# SR1PCB_2025-01-31.net
KiCad netlist of a schematic drawn in Altium Designer
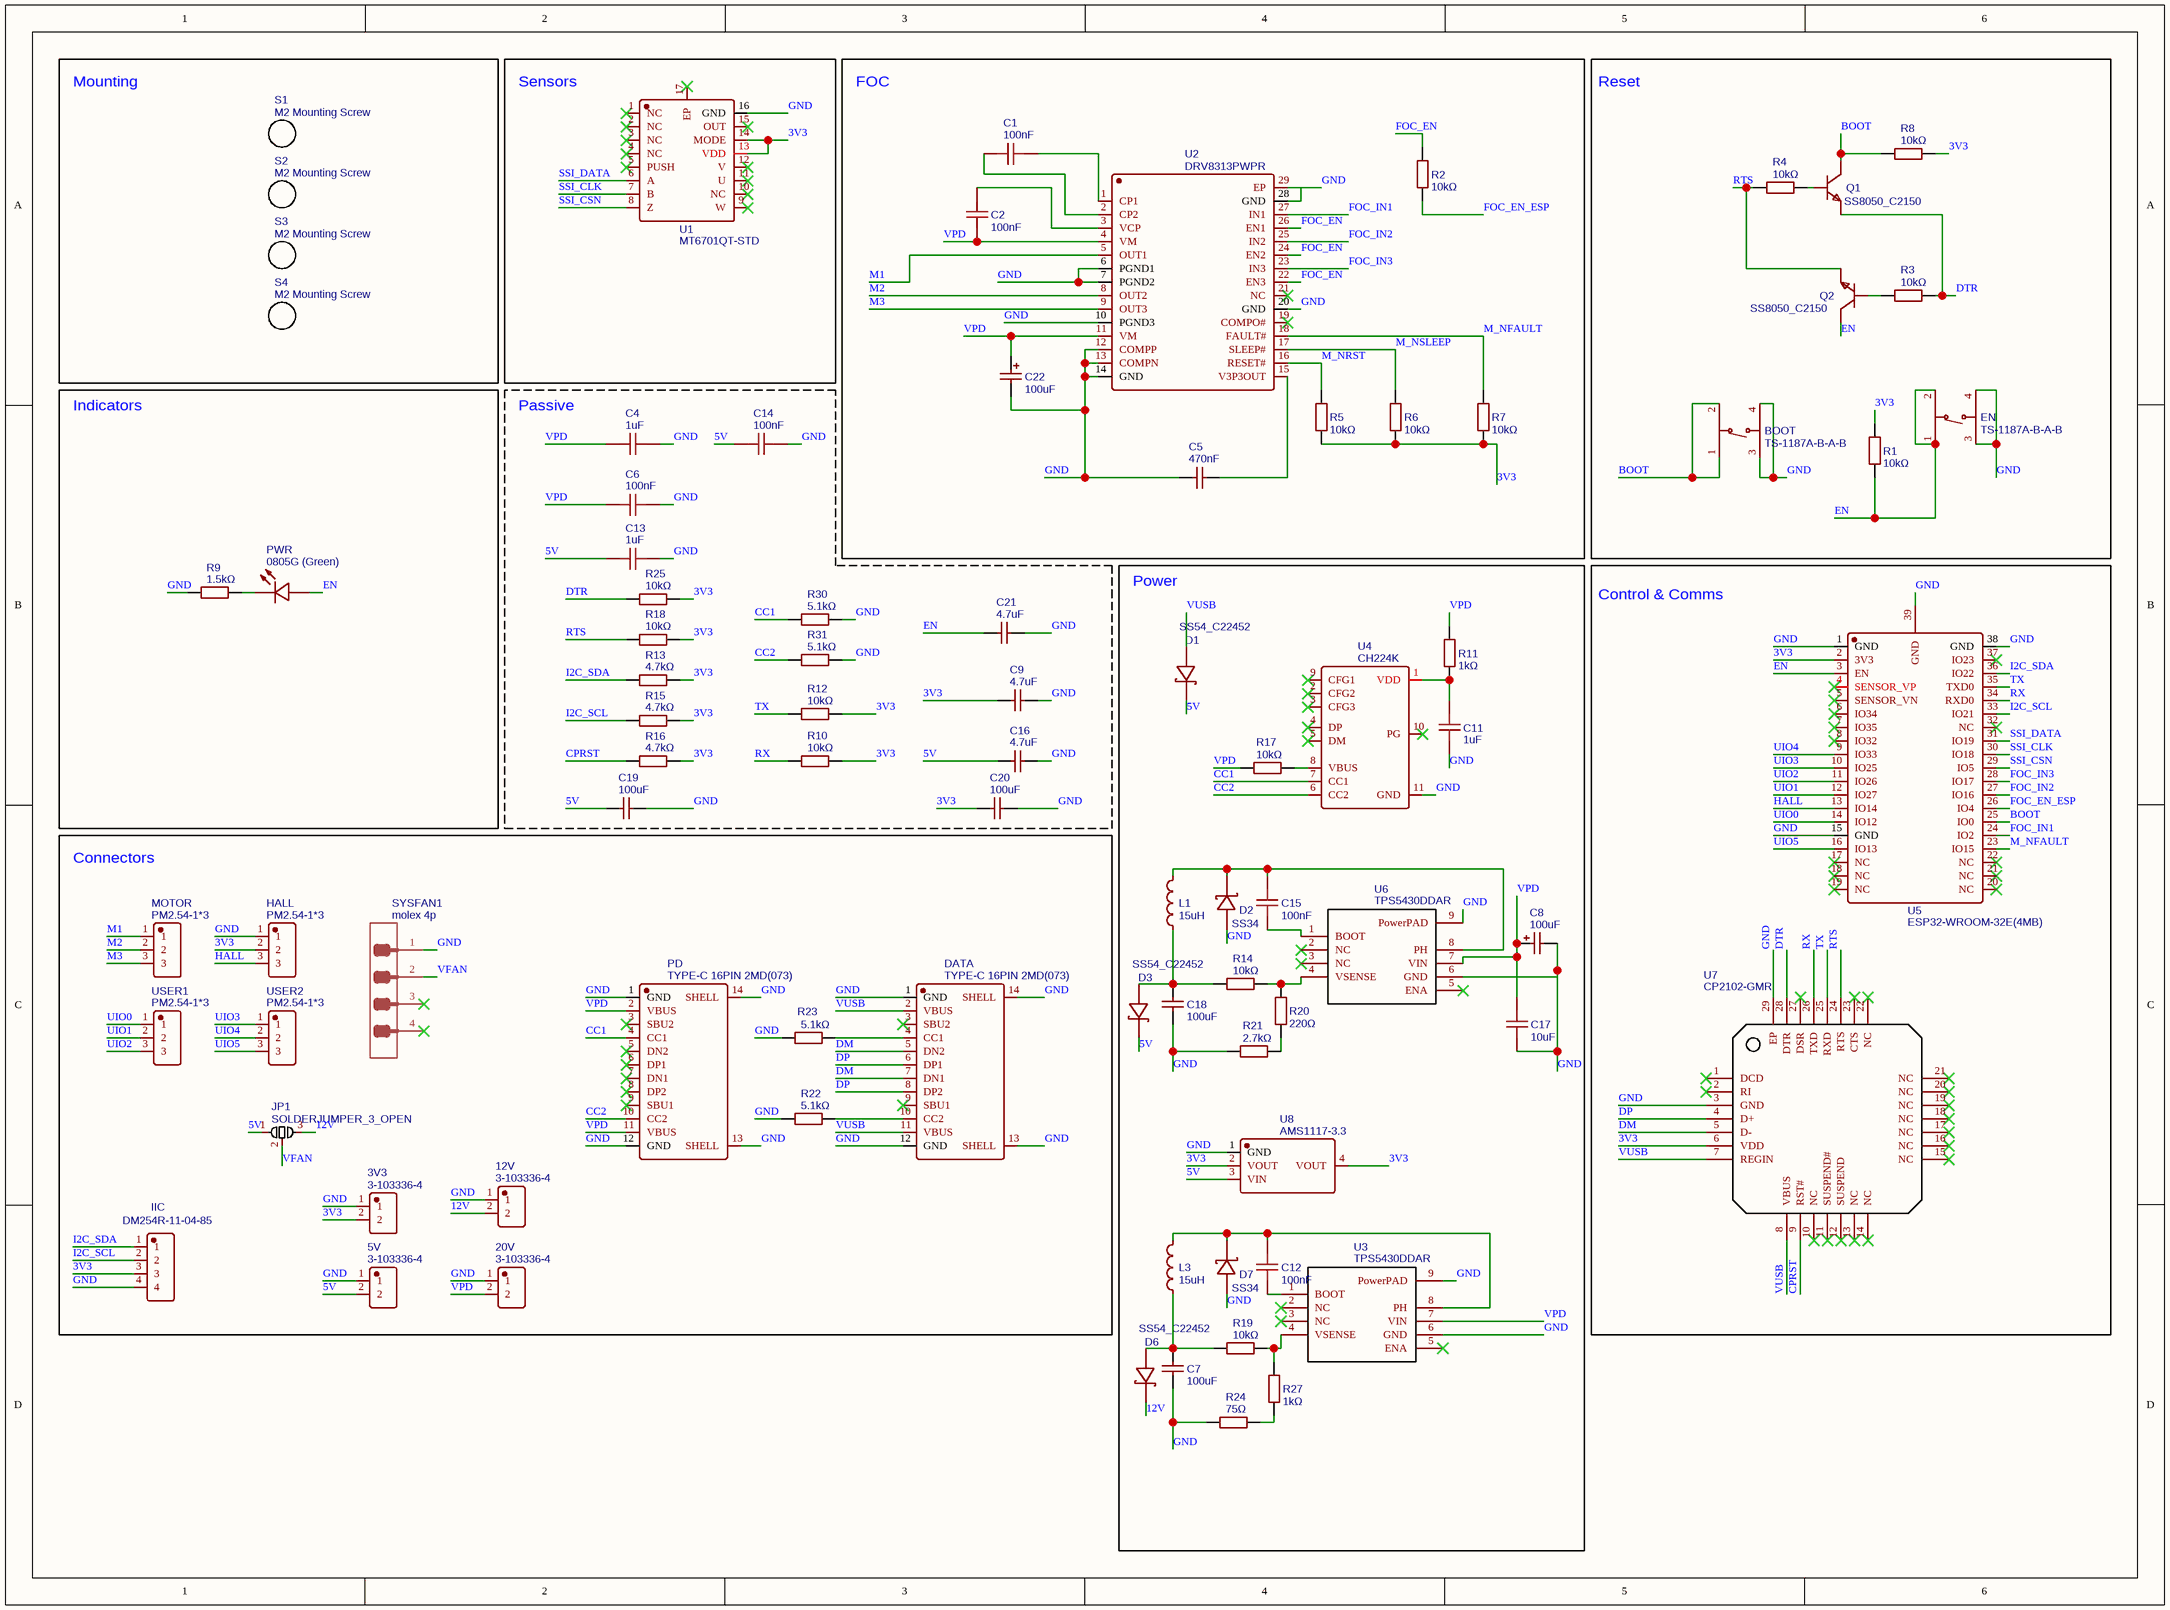
[diagram p0: SR1PCB_2025-01-31.schdoc]

(export (version "E")
  (design (tool "Eeschema 10.0.6"))
  (components
    (comp (ref "3V3")
      (value "3-103336-4")
      (fields (field (name "MANUFACTURER") "TE Connectivity(泰科电子)") (field (name "CONTRIBUTOR") "lcsc"))
      (libsource (lib "altium-import") (part "root_0_3-103336-4_"))
    )
    (comp (ref "5V")
      (value "3-103336-4")
      (fields (field (name "MANUFACTURER") "TE Connectivity(泰科电子)") (field (name "CONTRIBUTOR") "lcsc"))
      (libsource (lib "altium-import") (part "root_0_3-103336-4_"))
    )
    (comp (ref "12V")
      (value "3-103336-4")
      (fields (field (name "MANUFACTURER") "TE Connectivity(泰科电子)") (field (name "CONTRIBUTOR") "lcsc"))
      (libsource (lib "altium-import") (part "root_0_3-103336-4_"))
    )
    (comp (ref "20V")
      (value "3-103336-4")
      (fields (field (name "MANUFACTURER") "TE Connectivity(泰科电子)") (field (name "CONTRIBUTOR") "lcsc"))
      (libsource (lib "altium-import") (part "root_0_3-103336-4_"))
    )
    (comp (ref "BOOT")
      (value "TS-1187A-B-A-B")
      (fields (field (name "MANUFACTURER") "XKB Connectivity(中国星坤)") (field (name "CONTRIBUTOR") "LCSC"))
      (libsource (lib "altium-import") (part "root_1_TS-1187A-B-A-B_"))
    )
    (comp (ref "C1")
      (value "100nF")
      (fields
        (field (name "MANUFACTURER") "YAGEO(国巨)")
        (field (name "MANUFACTURER PART") "CC0603KRX7R9BB104")
      )
      (libsource (lib "altium-import") (part "root_0_100nF_"))
    )
    (comp (ref "C2")
      (value "100nF")
      (fields
        (field (name "MANUFACTURER") "YAGEO(国巨)")
        (field (name "MANUFACTURER PART") "CC0603KRX7R9BB104")
      )
      (libsource (lib "altium-import") (part "root_1_100nF_"))
    )
    (comp (ref "C4")
      (value "1uF")
      (fields
        (field (name "MANUFACTURER PART") "CL10A105KB8NNNC")
        (field (name "MANUFACTURER") "SAMSUNG(三星)")
      )
      (libsource (lib "altium-import") (part "root_0_1uF_"))
    )
    (comp (ref "C5")
      (value "470nF")
      (fields
        (field (name "MANUFACTURER PART") "CL21B474KBFNNNE")
        (field (name "MANUFACTURER") "SAMSUNG(三星)")
        (field (name "CONTRIBUTOR") "eisendev")
      )
      (libsource (lib "altium-import") (part "root_3_470nF_"))
    )
    (comp (ref "C6")
      (value "100nF")
      (fields
        (field (name "MANUFACTURER") "YAGEO(国巨)")
        (field (name "MANUFACTURER PART") "CC0603KRX7R9BB104")
      )
      (libsource (lib "altium-import") (part "root_0_100nF_"))
    )
    (comp (ref "C7")
      (value "100uF")
      (fields
        (field (name "MANUFACTURER PART") "CL31A107MQHNNNE")
        (field (name "MANUFACTURER") "SAMSUNG(三星)")
      )
      (libsource (lib "altium-import") (part "root_1_100uF_"))
    )
    (comp (ref "C8")
      (value "100uF")
      (fields (field (name "MANUFACTURER") "PANASONIC(松下)") (field (name "MANUFACTURER PART") "20TQC100MYF"))
      (libsource (lib "altium-import") (part "root_2_100uF_"))
    )
    (comp (ref "C9")
      (value "4.7uF")
      (fields
        (field (name "MANUFACTURER PART") "CL05A475MP5NRNC")
        (field (name "MANUFACTURER") "SAMSUNG(三星)")
      )
      (libsource (lib "altium-import") (part "root_0_4.7uF_"))
    )
    (comp (ref "C11")
      (value "1uF")
      (fields
        (field (name "MANUFACTURER PART") "CL10A105KB8NNNC")
        (field (name "MANUFACTURER") "SAMSUNG(三星)")
      )
      (libsource (lib "altium-import") (part "root_1_1uF_"))
    )
    (comp (ref "C12")
      (value "100nF")
      (fields
        (field (name "MANUFACTURER") "YAGEO(国巨)")
        (field (name "MANUFACTURER PART") "CC0603KRX7R9BB104")
      )
      (libsource (lib "altium-import") (part "root_3_100nF_"))
    )
    (comp (ref "C13")
      (value "1uF")
      (fields
        (field (name "MANUFACTURER PART") "CL10A105KB8NNNC")
        (field (name "MANUFACTURER") "SAMSUNG(三星)")
      )
      (libsource (lib "altium-import") (part "root_0_1uF_"))
    )
    (comp (ref "C14")
      (value "100nF")
      (fields
        (field (name "MANUFACTURER") "YAGEO(国巨)")
        (field (name "MANUFACTURER PART") "CC0603KRX7R9BB104")
      )
      (libsource (lib "altium-import") (part "root_0_100nF_"))
    )
    (comp (ref "C15")
      (value "100nF")
      (fields
        (field (name "MANUFACTURER") "YAGEO(国巨)")
        (field (name "MANUFACTURER PART") "CC0603KRX7R9BB104")
      )
      (libsource (lib "altium-import") (part "root_3_100nF_"))
    )
    (comp (ref "C16")
      (value "4.7uF")
      (fields
        (field (name "MANUFACTURER PART") "CL05A475MP5NRNC")
        (field (name "MANUFACTURER") "SAMSUNG(三星)")
      )
      (libsource (lib "altium-import") (part "root_0_4.7uF_"))
    )
    (comp (ref "C17")
      (value "10uF")
      (fields
        (field (name "MANUFACTURER PART") "CL21A106KAYNNNE")
        (field (name "MANUFACTURER") "SAMSUNG(三星)")
      )
      (libsource (lib "altium-import") (part "root_1_10uF_"))
    )
    (comp (ref "C18")
      (value "100uF")
      (fields
        (field (name "MANUFACTURER PART") "CL31A107MQHNNNE")
        (field (name "MANUFACTURER") "SAMSUNG(三星)")
      )
      (libsource (lib "altium-import") (part "root_1_100uF_"))
    )
    (comp (ref "C19")
      (value "100uF")
      (fields
        (field (name "MANUFACTURER PART") "CL31A107MQHNNNE")
        (field (name "MANUFACTURER") "SAMSUNG(三星)")
      )
      (libsource (lib "altium-import") (part "root_0_100uF_"))
    )
    (comp (ref "C20")
      (value "100uF")
      (fields
        (field (name "MANUFACTURER PART") "CL31A107MQHNNNE")
        (field (name "MANUFACTURER") "SAMSUNG(三星)")
      )
      (libsource (lib "altium-import") (part "root_0_100uF_"))
    )
    (comp (ref "C21")
      (value "4.7uF")
      (fields
        (field (name "MANUFACTURER PART") "CL05A475MP5NRNC")
        (field (name "MANUFACTURER") "SAMSUNG(三星)")
      )
      (libsource (lib "altium-import") (part "root_0_4.7uF_"))
    )
    (comp (ref "C22")
      (value "100uF")
      (fields (field (name "MANUFACTURER") "PANASONIC(松下)") (field (name "MANUFACTURER PART") "20TQC100MYF"))
      (libsource (lib "") (part "root_1_100uF__1"))
    )
    (comp (ref "D1")
      (value "SS54_C22452")
      (fields
        (field (name "MANUFACTURER PART") "SS54")
        (field (name "MANUFACTURER") "MDD")
        (field (name "CONTRIBUTOR") "mtz8302")
      )
      (libsource (lib "altium-import") (part "root_3_SS54_C22452_"))
    )
    (comp (ref "D2")
      (value "SS34")
      (fields (field (name "MANUFACTURER") "MDD(辰达半导体)"))
      (libsource (lib "altium-import") (part "root_3_SS34_"))
    )
    (comp (ref "D3")
      (value "SS54_C22452")
      (fields
        (field (name "MANUFACTURER PART") "SS54")
        (field (name "MANUFACTURER") "MDD")
        (field (name "CONTRIBUTOR") "mtz8302")
      )
      (libsource (lib "altium-import") (part "root_3_SS54_C22452_"))
    )
    (comp (ref "D6")
      (value "SS54_C22452")
      (fields
        (field (name "MANUFACTURER PART") "SS54")
        (field (name "MANUFACTURER") "MDD")
        (field (name "CONTRIBUTOR") "mtz8302")
      )
      (libsource (lib "altium-import") (part "root_3_SS54_C22452_"))
    )
    (comp (ref "D7")
      (value "SS34")
      (fields (field (name "MANUFACTURER") "MDD(辰达半导体)"))
      (libsource (lib "altium-import") (part "root_3_SS34_"))
    )
    (comp (ref "DATA")
      (value "TYPE-C 16PIN 2MD(073)")
      (fields (field (name "MANUFACTURER") "SHOU HAN(首韩)") (field (name "CONTRIBUTOR") "LCSC"))
      (libsource (lib "altium-import") (part "root_0_TYPE-C 16PIN 2MD(073)_"))
    )
    (comp (ref "EN")
      (value "TS-1187A-B-A-B")
      (fields (field (name "MANUFACTURER") "XKB Connectivity(中国星坤)") (field (name "CONTRIBUTOR") "LCSC"))
      (libsource (lib "altium-import") (part "root_1_TS-1187A-B-A-B_"))
    )
    (comp (ref "HALL")
      (value "PM2.54-1*3")
      (fields (field (name "MANUFACTURER") "ZHOURI(洲日)") (field (name "CONTRIBUTOR") "lcsc"))
      (libsource (lib "altium-import") (part "root_0_PM2.54-1*3_"))
    )
    (comp (ref "IIC")
      (value "DM254R-11-04-85")
      (fields (field (name "MANUFACTURER") "DEALON(德艺隆)") (field (name "CONTRIBUTOR") "LCSC"))
      (libsource (lib "altium-import") (part "root_0_DM254R-11-04-85_"))
    )
    (comp (ref "JP1")
      (value "SOLDERJUMPER_3_OPEN")
      (fields (field (name "CONTRIBUTOR") "mtz8302"))
      (libsource (lib "altium-import") (part "root_0_SOLDERJUMPER_3_OPEN_"))
    )
    (comp (ref "L1")
      (value "15uH")
      (fields
        (field (name "MANUFACTURER") "Sunlord(顺络)")
        (field (name "MANUFACTURER PART") "MWSA0603S-150MT")
        (field (name "CONTRIBUTOR") "LCSC")
      )
      (libsource (lib "altium-import") (part "root_1_15uH_"))
    )
    (comp (ref "L3")
      (value "15uH")
      (fields
        (field (name "MANUFACTURER") "Sunlord(顺络)")
        (field (name "MANUFACTURER PART") "MWSA0603S-150MT")
        (field (name "CONTRIBUTOR") "LCSC")
      )
      (libsource (lib "altium-import") (part "root_1_15uH_"))
    )
    (comp (ref "MOTOR")
      (value "PM2.54-1*3")
      (fields (field (name "MANUFACTURER") "ZHOURI(洲日)") (field (name "CONTRIBUTOR") "lcsc"))
      (libsource (lib "altium-import") (part "root_0_PM2.54-1*3_"))
    )
    (comp (ref "PD")
      (value "TYPE-C 16PIN 2MD(073)")
      (fields (field (name "MANUFACTURER") "SHOU HAN(首韩)") (field (name "CONTRIBUTOR") "LCSC"))
      (libsource (lib "altium-import") (part "root_0_TYPE-C 16PIN 2MD(073)_"))
    )
    (comp (ref "PWR")
      (value "0805G (Green)")
      (fields (field (name "MANUFACTURER") "KENTO") (field (name "MANUFACTURER PART") "KT-0805G"))
      (libsource (lib "altium-import") (part "root_0_0805G (Green)_"))
    )
    (comp (ref "Q1")
      (value "SS8050_C2150")
      (fields (field (name "MANUFACTURER") "CJ(江苏长电/长晶)") (field (name "MANUFACTURER PART") "SS8050"))
      (libsource (lib "altium-import") (part "root_0_SS8050_C2150_"))
    )
    (comp (ref "Q2")
      (value "SS8050_C2150")
      (fields (field (name "MANUFACTURER") "CJ(江苏长电/长晶)") (field (name "MANUFACTURER PART") "SS8050"))
      (libsource (lib "altium-import") (part "root_2_SS8050_C2150_"))
    )
    (comp (ref "R1")
      (value "10kΩ")
      (fields
        (field (name "MANUFACTURER") "UNI-ROYAL(厚声)")
        (field (name "MANUFACTURER PART") "0402WGF1002TCE")
      )
      (libsource (lib "altium-import") (part "root_1_10kΩ_"))
    )
    (comp (ref "R2")
      (value "10kΩ")
      (fields
        (field (name "MANUFACTURER") "UNI-ROYAL(厚声)")
        (field (name "MANUFACTURER PART") "0603WAF1002T5E")
      )
      (libsource (lib "altium-import") (part "root_1_10kΩ_"))
    )
    (comp (ref "R3")
      (value "10kΩ")
      (fields
        (field (name "MANUFACTURER") "UNI-ROYAL(厚声)")
        (field (name "MANUFACTURER PART") "0402WGF1002TCE")
      )
      (libsource (lib "altium-import") (part "root_2_10kΩ_"))
    )
    (comp (ref "R4")
      (value "10kΩ")
      (fields
        (field (name "MANUFACTURER") "UNI-ROYAL(厚声)")
        (field (name "MANUFACTURER PART") "0402WGF1002TCE")
      )
      (libsource (lib "altium-import") (part "root_2_10kΩ_"))
    )
    (comp (ref "R5")
      (value "10kΩ")
      (fields
        (field (name "MANUFACTURER") "UNI-ROYAL(厚声)")
        (field (name "MANUFACTURER PART") "0402WGF1002TCE")
      )
      (libsource (lib "altium-import") (part "root_1_10kΩ_"))
    )
    (comp (ref "R6")
      (value "10kΩ")
      (fields
        (field (name "MANUFACTURER") "UNI-ROYAL(厚声)")
        (field (name "MANUFACTURER PART") "0402WGF1002TCE")
      )
      (libsource (lib "altium-import") (part "root_1_10kΩ_"))
    )
    (comp (ref "R7")
      (value "10kΩ")
      (fields
        (field (name "MANUFACTURER") "UNI-ROYAL(厚声)")
        (field (name "MANUFACTURER PART") "0402WGF1002TCE")
      )
      (libsource (lib "altium-import") (part "root_1_10kΩ_"))
    )
    (comp (ref "R8")
      (value "10kΩ")
      (fields
        (field (name "MANUFACTURER") "UNI-ROYAL(厚声)")
        (field (name "MANUFACTURER PART") "0402WGF1002TCE")
      )
      (libsource (lib "altium-import") (part "root_2_10kΩ_"))
    )
    (comp (ref "R9")
      (value "1.5kΩ")
      (fields
        (field (name "MANUFACTURER") "UNI-ROYAL(厚声)")
        (field (name "MANUFACTURER PART") "0603WAF1501T5E")
      )
      (libsource (lib "altium-import") (part "root_0_1.5kΩ_"))
    )
    (comp (ref "R10")
      (value "10kΩ")
      (fields
        (field (name "MANUFACTURER") "UNI-ROYAL(厚声)")
        (field (name "MANUFACTURER PART") "0402WGF1002TCE")
      )
      (libsource (lib "altium-import") (part "root_0_10kΩ_"))
    )
    (comp (ref "R11")
      (value "1kΩ")
      (fields
        (field (name "MANUFACTURER") "UNI-ROYAL(厚声)")
        (field (name "MANUFACTURER PART") "0402WGF1001TCE")
      )
      (libsource (lib "altium-import") (part "root_1_1kΩ_"))
    )
    (comp (ref "R12")
      (value "10kΩ")
      (fields
        (field (name "MANUFACTURER") "UNI-ROYAL(厚声)")
        (field (name "MANUFACTURER PART") "0402WGF1002TCE")
      )
      (libsource (lib "altium-import") (part "root_0_10kΩ_"))
    )
    (comp (ref "R13")
      (value "4.7kΩ")
      (fields
        (field (name "MANUFACTURER") "UNI-ROYAL(厚声)")
        (field (name "MANUFACTURER PART") "0402WGF4701TCE")
      )
      (libsource (lib "altium-import") (part "root_0_4.7kΩ_"))
    )
    (comp (ref "R14")
      (value "10kΩ")
      (fields
        (field (name "MANUFACTURER") "UNI-ROYAL(厚声)")
        (field (name "MANUFACTURER PART") "0402WGF1002TCE")
      )
      (libsource (lib "altium-import") (part "root_0_10kΩ_"))
    )
    (comp (ref "R15")
      (value "4.7kΩ")
      (fields
        (field (name "MANUFACTURER") "UNI-ROYAL(厚声)")
        (field (name "MANUFACTURER PART") "0402WGF4701TCE")
      )
      (libsource (lib "altium-import") (part "root_0_4.7kΩ_"))
    )
    (comp (ref "R16")
      (value "4.7kΩ")
      (fields
        (field (name "MANUFACTURER") "UNI-ROYAL(厚声)")
        (field (name "MANUFACTURER PART") "0402WGF4701TCE")
      )
      (libsource (lib "altium-import") (part "root_0_4.7kΩ_"))
    )
    (comp (ref "R17")
      (value "10kΩ")
      (fields
        (field (name "MANUFACTURER") "UNI-ROYAL(厚声)")
        (field (name "MANUFACTURER PART") "0402WGF1002TCE")
      )
      (libsource (lib "altium-import") (part "root_2_10kΩ_"))
    )
    (comp (ref "R18")
      (value "10kΩ")
      (fields
        (field (name "MANUFACTURER") "UNI-ROYAL(厚声)")
        (field (name "MANUFACTURER PART") "0402WGF1002TCE")
      )
      (libsource (lib "altium-import") (part "root_0_10kΩ_"))
    )
    (comp (ref "R19")
      (value "10kΩ")
      (fields
        (field (name "MANUFACTURER") "UNI-ROYAL(厚声)")
        (field (name "MANUFACTURER PART") "0402WGF1002TCE")
      )
      (libsource (lib "altium-import") (part "root_0_10kΩ_"))
    )
    (comp (ref "R20")
      (value "220Ω")
      (fields
        (field (name "MANUFACTURER") "UNI-ROYAL(厚声)")
        (field (name "MANUFACTURER PART") "0603WAF2200T5E")
      )
      (libsource (lib "altium-import") (part "root_1_220Ω_"))
    )
    (comp (ref "R21")
      (value "2.7kΩ")
      (fields
        (field (name "MANUFACTURER") "UniOhm")
        (field (name "MANUFACTURER PART") "0603WAF2701T5E")
        (field (name "CONTRIBUTOR") "kliu24")
      )
      (libsource (lib "altium-import") (part "root_0_2.7kΩ_"))
    )
    (comp (ref "R22")
      (value "5.1kΩ")
      (fields
        (field (name "MANUFACTURER") "UNI-ROYAL(厚声)")
        (field (name "MANUFACTURER PART") "0402WGF5101TCE")
      )
      (libsource (lib "altium-import") (part "root_0_5.1kΩ_"))
    )
    (comp (ref "R23")
      (value "5.1kΩ")
      (fields
        (field (name "MANUFACTURER") "UNI-ROYAL(厚声)")
        (field (name "MANUFACTURER PART") "0402WGF5101TCE")
      )
      (libsource (lib "altium-import") (part "root_0_5.1kΩ_"))
    )
    (comp (ref "R24")
      (value "75Ω")
      (fields
        (field (name "MANUFACTURER") "UNI-ROYAL(厚声)")
        (field (name "MANUFACTURER PART") "0603WAF750JT5E")
      )
      (libsource (lib "altium-import") (part "root_0_75Ω_"))
    )
    (comp (ref "R25")
      (value "10kΩ")
      (fields
        (field (name "MANUFACTURER") "UNI-ROYAL(厚声)")
        (field (name "MANUFACTURER PART") "0402WGF1002TCE")
      )
      (libsource (lib "altium-import") (part "root_0_10kΩ_"))
    )
    (comp (ref "R27")
      (value "1kΩ")
      (fields
        (field (name "MANUFACTURER") "UNI-ROYAL(厚声)")
        (field (name "MANUFACTURER PART") "0603WAF1001T5E")
      )
      (libsource (lib "altium-import") (part "root_1_1kΩ_"))
    )
    (comp (ref "R30")
      (value "5.1kΩ")
      (fields
        (field (name "MANUFACTURER") "UNI-ROYAL(厚声)")
        (field (name "MANUFACTURER PART") "0402WGF5101TCE")
      )
      (libsource (lib "altium-import") (part "root_0_5.1kΩ_"))
    )
    (comp (ref "R31")
      (value "5.1kΩ")
      (fields
        (field (name "MANUFACTURER") "UNI-ROYAL(厚声)")
        (field (name "MANUFACTURER PART") "0402WGF5101TCE")
      )
      (libsource (lib "altium-import") (part "root_0_5.1kΩ_"))
    )
    (comp (ref "S1")
      (value "M2 Mounting Screw")
      (fields (field (name "CONTRIBUTOR") "Dayat -"))
      (libsource (lib "altium-import") (part "root_0_M2 Mounting Screw_"))
    )
    (comp (ref "S2")
      (value "M2 Mounting Screw")
      (fields (field (name "CONTRIBUTOR") "Dayat -"))
      (libsource (lib "altium-import") (part "root_0_M2 Mounting Screw_"))
    )
    (comp (ref "S3")
      (value "M2 Mounting Screw")
      (fields (field (name "CONTRIBUTOR") "Dayat -"))
      (libsource (lib "altium-import") (part "root_0_M2 Mounting Screw_"))
    )
    (comp (ref "S4")
      (value "M2 Mounting Screw")
      (fields (field (name "CONTRIBUTOR") "Dayat -"))
      (libsource (lib "altium-import") (part "root_0_M2 Mounting Screw_"))
    )
    (comp (ref "SYSFAN1")
      (value "molex 4p")
      (fields (field (name "CONTRIBUTOR") "delil1220"))
      (libsource (lib "altium-import") (part "root_0_molex 4p_"))
    )
    (comp (ref "U1")
      (value "MT6701QT-STD")
      (fields (field (name "MANUFACTURER") "MagnTek(麦歌恩)") (field (name "CONTRIBUTOR") "LCSC"))
      (libsource (lib "altium-import") (part "root_0_MT6701QT-STD_"))
    )
    (comp (ref "U2")
      (value "DRV8313PWPR")
      (fields (field (name "MANUFACTURER") "Texas Instruments") (field (name "CONTRIBUTOR") "LCSC"))
      (libsource (lib "altium-import") (part "root_0_DRV8313PWPR_"))
    )
    (comp (ref "U3")
      (value "TPS5430DDAR")
      (fields (field (name "MANUFACTURER") "TI(德州仪器)"))
      (libsource (lib "altium-import") (part "root_0_TPS5430DDAR_"))
    )
    (comp (ref "U4")
      (value "CH224K")
      (fields (field (name "MANUFACTURER") "WCH(南京沁恒)") (field (name "CONTRIBUTOR") "lcsc"))
      (libsource (lib "altium-import") (part "root_0_CH224K_"))
    )
    (comp (ref "U5")
      (value "ESP32-WROOM-32E(4MB)")
      (fields
        (field (name "MANUFACTURER") "ESPRESSIF(乐鑫)")
        (field (name "MANUFACTURER PART") "ESP32-WROOM-32E-N4")
        (field (name "CONTRIBUTOR") "LCSC")
      )
      (libsource (lib "altium-import") (part "root_0_ESP32-WROOM-32E(4MB)_"))
    )
    (comp (ref "U6")
      (value "TPS5430DDAR")
      (fields (field (name "MANUFACTURER") "TI(德州仪器)"))
      (libsource (lib "altium-import") (part "root_0_TPS5430DDAR_"))
    )
    (comp (ref "U7")
      (value "CP2102-GMR")
      (fields (field (name "MANUFACTURER") "SKYWORKS/SILICON LABS(芯科)"))
      (libsource (lib "altium-import") (part "root_0_CP2102-GMR_"))
    )
    (comp (ref "U8")
      (value "AMS1117-3.3")
      (fields (field (name "MANUFACTURER") "AMS"))
      (libsource (lib "altium-import") (part "root_0_AMS1117-3.3_"))
    )
    (comp (ref "USER1")
      (value "PM2.54-1*3")
      (fields (field (name "MANUFACTURER") "ZHOURI(洲日)") (field (name "CONTRIBUTOR") "lcsc"))
      (libsource (lib "altium-import") (part "root_0_PM2.54-1*3_"))
    )
    (comp (ref "USER2")
      (value "PM2.54-1*3")
      (fields (field (name "MANUFACTURER") "ZHOURI(洲日)") (field (name "CONTRIBUTOR") "lcsc"))
      (libsource (lib "altium-import") (part "root_0_PM2.54-1*3_"))
    )
  )
  (nets
    (net (code "1") (name "/3V3") (class "Default")
      (node (ref "3V3") (pin "2") (pinfunction "2_2") (pintype "passive"))
      (node (ref "C20") (pin "1") (pinfunction "1_1") (pintype "passive"))
      (node (ref "C9") (pin "1") (pinfunction "1_1") (pintype "passive"))
      (node (ref "HALL") (pin "2") (pinfunction "2_2") (pintype "passive"))
      (node (ref "IIC") (pin "3") (pinfunction "3_3") (pintype "passive"))
      (node (ref "R1") (pin "2") (pinfunction "2_2") (pintype "passive"))
      (node (ref "R10") (pin "2") (pinfunction "2_2") (pintype "passive"))
      (node (ref "R12") (pin "2") (pinfunction "2_2") (pintype "passive"))
      (node (ref "R13") (pin "2") (pinfunction "2_2") (pintype "passive"))
      (node (ref "R15") (pin "2") (pinfunction "2_2") (pintype "passive"))
      (node (ref "R16") (pin "2") (pinfunction "2_2") (pintype "passive"))
      (node (ref "R18") (pin "2") (pinfunction "2_2") (pintype "passive"))
      (node (ref "R25") (pin "2") (pinfunction "2_2") (pintype "passive"))
      (node (ref "R5") (pin "1") (pinfunction "1_1") (pintype "passive"))
      (node (ref "R6") (pin "1") (pinfunction "1_1") (pintype "passive"))
      (node (ref "R7") (pin "1") (pinfunction "1_1") (pintype "passive"))
      (node (ref "R8") (pin "1") (pinfunction "1_1") (pintype "passive"))
      (node (ref "U1") (pin "13") (pinfunction "VDD_13") (pintype "passive"))
      (node (ref "U1") (pin "14") (pinfunction "MODE_14") (pintype "passive"))
      (node (ref "U5") (pin "2") (pinfunction "3V3_2") (pintype "passive"))
      (node (ref "U7") (pin "6") (pinfunction "VDD_6") (pintype "passive"))
      (node (ref "U8") (pin "2") (pinfunction "VOUT_2") (pintype "passive"))
      (node (ref "U8") (pin "4") (pinfunction "VOUT_4") (pintype "passive"))
    )
    (net (code "2") (name "/5V") (class "Default")
      (node (ref "5V") (pin "2") (pinfunction "2_2") (pintype "passive"))
      (node (ref "C13") (pin "1") (pinfunction "1_1") (pintype "passive"))
      (node (ref "C14") (pin "1") (pinfunction "1_1") (pintype "passive"))
      (node (ref "C16") (pin "1") (pinfunction "1_1") (pintype "passive"))
      (node (ref "C19") (pin "1") (pinfunction "1_1") (pintype "passive"))
      (node (ref "D1") (pin "2") (pinfunction "K_2") (pintype "passive"))
      (node (ref "D3") (pin "2") (pinfunction "K_2") (pintype "passive"))
      (node (ref "JP1") (pin "1") (pinfunction "A_1") (pintype "passive"))
      (node (ref "U8") (pin "3") (pinfunction "VIN_3") (pintype "passive"))
    )
    (net (code "3") (name "/12V") (class "Default")
      (node (ref "12V") (pin "2") (pinfunction "2_2") (pintype "passive"))
      (node (ref "D6") (pin "2") (pinfunction "K_2") (pintype "passive"))
      (node (ref "JP1") (pin "3") (pinfunction "B_3") (pintype "passive"))
    )
    (net (code "4") (name "/BOOT") (class "Default")
      (node (ref "BOOT") (pin "1") (pinfunction "A_1") (pintype "passive"))
      (node (ref "BOOT") (pin "2") (pinfunction "B_2") (pintype "passive"))
      (node (ref "Q1") (pin "3") (pinfunction "C_3") (pintype "passive"))
      (node (ref "R8") (pin "2") (pinfunction "2_2") (pintype "passive"))
      (node (ref "U5") (pin "25") (pinfunction "IO0_25") (pintype "passive"))
    )
    (net (code "5") (name "/CC1") (class "Default")
      (node (ref "PD") (pin "4") (pinfunction "CC1_4") (pintype "passive"))
      (node (ref "R30") (pin "1") (pinfunction "1_1") (pintype "passive"))
      (node (ref "U4") (pin "7") (pinfunction "CC1_7") (pintype "passive"))
    )
    (net (code "6") (name "/CC2") (class "Default")
      (node (ref "PD") (pin "10") (pinfunction "CC2_10") (pintype "passive"))
      (node (ref "R31") (pin "1") (pinfunction "1_1") (pintype "passive"))
      (node (ref "U4") (pin "6") (pinfunction "CC2_6") (pintype "passive"))
    )
    (net (code "7") (name "/CPRST") (class "Default")
      (node (ref "R16") (pin "1") (pinfunction "1_1") (pintype "passive"))
      (node (ref "U7") (pin "9") (pinfunction "RST#_9") (pintype "passive"))
    )
    (net (code "8") (name "/DM") (class "Default")
      (node (ref "DATA") (pin "5") (pinfunction "DN2_5") (pintype "passive"))
      (node (ref "DATA") (pin "7") (pinfunction "DN1_7") (pintype "passive"))
      (node (ref "U7") (pin "5") (pinfunction "D-_5") (pintype "passive"))
    )
    (net (code "9") (name "/DP") (class "Default")
      (node (ref "DATA") (pin "6") (pinfunction "DP1_6") (pintype "passive"))
      (node (ref "DATA") (pin "8") (pinfunction "DP2_8") (pintype "passive"))
      (node (ref "U7") (pin "4") (pinfunction "D+_4") (pintype "passive"))
    )
    (net (code "10") (name "/DTR") (class "Default")
      (node (ref "Q1") (pin "2") (pinfunction "E_2") (pintype "passive"))
      (node (ref "R25") (pin "1") (pinfunction "1_1") (pintype "passive"))
      (node (ref "R3") (pin "1") (pinfunction "1_1") (pintype "passive"))
      (node (ref "U7") (pin "28") (pinfunction "DTR_28") (pintype "passive"))
    )
    (net (code "11") (name "/EN") (class "Default")
      (node (ref "C21") (pin "1") (pinfunction "1_1") (pintype "passive"))
      (node (ref "EN") (pin "1") (pinfunction "A_1") (pintype "passive"))
      (node (ref "EN") (pin "2") (pinfunction "B_2") (pintype "passive"))
      (node (ref "PWR") (pin "1") (pinfunction "A_1") (pintype "passive"))
      (node (ref "Q2") (pin "3") (pinfunction "C_3") (pintype "passive"))
      (node (ref "R1") (pin "1") (pinfunction "1_1") (pintype "passive"))
      (node (ref "U5") (pin "3") (pinfunction "EN_3") (pintype "passive"))
    )
    (net (code "12") (name "/FOC_EN") (class "Default")
      (node (ref "R2") (pin "2") (pinfunction "2_2") (pintype "passive"))
      (node (ref "U2") (pin "22") (pinfunction "EN3_22") (pintype "passive"))
      (node (ref "U2") (pin "24") (pinfunction "EN2_24") (pintype "passive"))
      (node (ref "U2") (pin "26") (pinfunction "EN1_26") (pintype "passive"))
    )
    (net (code "13") (name "/FOC_EN_ESP") (class "Default")
      (node (ref "R2") (pin "1") (pinfunction "1_1") (pintype "passive"))
      (node (ref "U5") (pin "26") (pinfunction "IO4_26") (pintype "passive"))
    )
    (net (code "14") (name "/FOC_IN1") (class "Default")
      (node (ref "U2") (pin "27") (pinfunction "IN1_27") (pintype "passive"))
      (node (ref "U5") (pin "24") (pinfunction "IO2_24") (pintype "passive"))
    )
    (net (code "15") (name "/FOC_IN2") (class "Default")
      (node (ref "U2") (pin "25") (pinfunction "IN2_25") (pintype "passive"))
      (node (ref "U5") (pin "27") (pinfunction "IO16_27") (pintype "passive"))
    )
    (net (code "16") (name "/FOC_IN3") (class "Default")
      (node (ref "U2") (pin "23") (pinfunction "IN3_23") (pintype "passive"))
      (node (ref "U5") (pin "28") (pinfunction "IO17_28") (pintype "passive"))
    )
    (net (code "17") (name "/GND") (class "Default")
      (node (ref "12V") (pin "1") (pinfunction "1_1") (pintype "passive"))
      (node (ref "20V") (pin "1") (pinfunction "1_1") (pintype "passive"))
      (node (ref "3V3") (pin "1") (pinfunction "1_1") (pintype "passive"))
      (node (ref "5V") (pin "1") (pinfunction "1_1") (pintype "passive"))
      (node (ref "BOOT") (pin "3") (pinfunction "C_3") (pintype "passive"))
      (node (ref "BOOT") (pin "4") (pinfunction "D_4") (pintype "passive"))
      (node (ref "C11") (pin "1") (pinfunction "1_1") (pintype "passive"))
      (node (ref "C13") (pin "2") (pinfunction "2_2") (pintype "passive"))
      (node (ref "C14") (pin "2") (pinfunction "2_2") (pintype "passive"))
      (node (ref "C16") (pin "2") (pinfunction "2_2") (pintype "passive"))
      (node (ref "C17") (pin "1") (pinfunction "1_1") (pintype "passive"))
      (node (ref "C18") (pin "1") (pinfunction "1_1") (pintype "passive"))
      (node (ref "C19") (pin "2") (pinfunction "2_2") (pintype "passive"))
      (node (ref "C20") (pin "2") (pinfunction "2_2") (pintype "passive"))
      (node (ref "C21") (pin "2") (pinfunction "2_2") (pintype "passive"))
      (node (ref "C22") (pin "2") (pinfunction "2_2") (pintype "passive"))
      (node (ref "C4") (pin "2") (pinfunction "2_2") (pintype "passive"))
      (node (ref "C5") (pin "1") (pinfunction "1_1") (pintype "passive"))
      (node (ref "C6") (pin "2") (pinfunction "2_2") (pintype "passive"))
      (node (ref "C7") (pin "1") (pinfunction "1_1") (pintype "passive"))
      (node (ref "C8") (pin "2") (pinfunction "2_2") (pintype "passive"))
      (node (ref "C9") (pin "2") (pinfunction "2_2") (pintype "passive"))
      (node (ref "D2") (pin "2") (pinfunction "A_2") (pintype "passive"))
      (node (ref "D7") (pin "2") (pinfunction "A_2") (pintype "passive"))
      (node (ref "DATA") (pin "1") (pinfunction "GND_1") (pintype "passive"))
      (node (ref "DATA") (pin "12") (pinfunction "GND_12") (pintype "passive"))
      (node (ref "DATA") (pin "13") (pinfunction "SHELL_13") (pintype "passive"))
      (node (ref "DATA") (pin "14") (pinfunction "SHELL_14") (pintype "passive"))
      (node (ref "EN") (pin "3") (pinfunction "C_3") (pintype "passive"))
      (node (ref "EN") (pin "4") (pinfunction "D_4") (pintype "passive"))
      (node (ref "HALL") (pin "1") (pinfunction "1_1") (pintype "passive"))
      (node (ref "IIC") (pin "4") (pinfunction "4_4") (pintype "passive"))
      (node (ref "PD") (pin "1") (pinfunction "GND_1") (pintype "passive"))
      (node (ref "PD") (pin "12") (pinfunction "GND_12") (pintype "passive"))
      (node (ref "PD") (pin "13") (pinfunction "SHELL_13") (pintype "passive"))
      (node (ref "PD") (pin "14") (pinfunction "SHELL_14") (pintype "passive"))
      (node (ref "R21") (pin "2") (pinfunction "2_2") (pintype "passive"))
      (node (ref "R22") (pin "1") (pinfunction "1_1") (pintype "passive"))
      (node (ref "R23") (pin "1") (pinfunction "1_1") (pintype "passive"))
      (node (ref "R24") (pin "1") (pinfunction "1_1") (pintype "passive"))
      (node (ref "R30") (pin "2") (pinfunction "2_2") (pintype "passive"))
      (node (ref "R31") (pin "2") (pinfunction "2_2") (pintype "passive"))
      (node (ref "R9") (pin "1") (pinfunction "1_1") (pintype "passive"))
      (node (ref "SYSFAN1") (pin "1") (pinfunction "1_1") (pintype "passive"))
      (node (ref "U1") (pin "16") (pinfunction "GND_16") (pintype "passive"))
      (node (ref "U2") (pin "10") (pinfunction "PGND3_10") (pintype "passive"))
      (node (ref "U2") (pin "12") (pinfunction "COMPP_12") (pintype "passive"))
      (node (ref "U2") (pin "13") (pinfunction "COMPN_13") (pintype "passive"))
      (node (ref "U2") (pin "14") (pinfunction "GND_14") (pintype "passive"))
      (node (ref "U2") (pin "20") (pinfunction "GND_20") (pintype "passive"))
      (node (ref "U2") (pin "28") (pinfunction "GND_28") (pintype "passive"))
      (node (ref "U2") (pin "29") (pinfunction "EP_29") (pintype "passive"))
      (node (ref "U2") (pin "6") (pinfunction "PGND1_6") (pintype "passive"))
      (node (ref "U2") (pin "7") (pinfunction "PGND2_7") (pintype "passive"))
      (node (ref "U3") (pin "6") (pinfunction "GND_6") (pintype "passive"))
      (node (ref "U3") (pin "9") (pinfunction "PowerPAD_9") (pintype "passive"))
      (node (ref "U4") (pin "11") (pinfunction "GND_11") (pintype "passive"))
      (node (ref "U5") (pin "1") (pinfunction "GND_1") (pintype "passive"))
      (node (ref "U5") (pin "15") (pinfunction "GND_15") (pintype "passive"))
      (node (ref "U5") (pin "38") (pinfunction "GND_38") (pintype "passive"))
      (node (ref "U5") (pin "39") (pinfunction "GND_39") (pintype "passive"))
      (node (ref "U6") (pin "6") (pinfunction "GND_6") (pintype "passive"))
      (node (ref "U6") (pin "9") (pinfunction "PowerPAD_9") (pintype "passive"))
      (node (ref "U7") (pin "29") (pinfunction "EP_29") (pintype "passive"))
      (node (ref "U7") (pin "3") (pinfunction "GND_3") (pintype "passive"))
      (node (ref "U8") (pin "1") (pinfunction "GND_1") (pintype "passive"))
    )
    (net (code "18") (name "/HALL") (class "Default")
      (node (ref "HALL") (pin "3") (pinfunction "3_3") (pintype "passive"))
      (node (ref "U5") (pin "13") (pinfunction "IO14_13") (pintype "passive"))
    )
    (net (code "19") (name "/I2C_SCL") (class "Default")
      (node (ref "IIC") (pin "2") (pinfunction "2_2") (pintype "passive"))
      (node (ref "R15") (pin "1") (pinfunction "1_1") (pintype "passive"))
      (node (ref "U5") (pin "33") (pinfunction "IO21_33") (pintype "passive"))
    )
    (net (code "20") (name "/I2C_SDA") (class "Default")
      (node (ref "IIC") (pin "1") (pinfunction "1_1") (pintype "passive"))
      (node (ref "R13") (pin "1") (pinfunction "1_1") (pintype "passive"))
      (node (ref "U5") (pin "36") (pinfunction "IO22_36") (pintype "passive"))
    )
    (net (code "21") (name "/M1") (class "Default")
      (node (ref "MOTOR") (pin "1") (pinfunction "1_1") (pintype "passive"))
      (node (ref "U2") (pin "5") (pinfunction "OUT1_5") (pintype "passive"))
    )
    (net (code "22") (name "/M2") (class "Default")
      (node (ref "MOTOR") (pin "2") (pinfunction "2_2") (pintype "passive"))
      (node (ref "U2") (pin "8") (pinfunction "OUT2_8") (pintype "passive"))
    )
    (net (code "23") (name "/M3") (class "Default")
      (node (ref "MOTOR") (pin "3") (pinfunction "3_3") (pintype "passive"))
      (node (ref "U2") (pin "9") (pinfunction "OUT3_9") (pintype "passive"))
    )
    (net (code "24") (name "/M_NFAULT") (class "Default")
      (node (ref "R7") (pin "2") (pinfunction "2_2") (pintype "passive"))
      (node (ref "U2") (pin "18") (pinfunction "FAULT#_18") (pintype "passive"))
      (node (ref "U5") (pin "23") (pinfunction "IO15_23") (pintype "passive"))
    )
    (net (code "25") (name "/M_NRST") (class "Default")
      (node (ref "R5") (pin "2") (pinfunction "2_2") (pintype "passive"))
      (node (ref "U2") (pin "16") (pinfunction "RESET#_16") (pintype "passive"))
    )
    (net (code "26") (name "/M_NSLEEP") (class "Default")
      (node (ref "R6") (pin "2") (pinfunction "2_2") (pintype "passive"))
      (node (ref "U2") (pin "17") (pinfunction "SLEEP#_17") (pintype "passive"))
    )
    (net (code "27") (name "/RTS") (class "Default")
      (node (ref "Q2") (pin "2") (pinfunction "E_2") (pintype "passive"))
      (node (ref "R18") (pin "1") (pinfunction "1_1") (pintype "passive"))
      (node (ref "R4") (pin "2") (pinfunction "2_2") (pintype "passive"))
      (node (ref "U7") (pin "24") (pinfunction "RTS_24") (pintype "passive"))
    )
    (net (code "28") (name "/RX") (class "Default")
      (node (ref "R10") (pin "1") (pinfunction "1_1") (pintype "passive"))
      (node (ref "U5") (pin "34") (pinfunction "RXD0_34") (pintype "passive"))
      (node (ref "U7") (pin "26") (pinfunction "TXD_26") (pintype "passive"))
    )
    (net (code "29") (name "/SSI_CLK") (class "Default")
      (node (ref "U1") (pin "7") (pinfunction "B_7") (pintype "passive"))
      (node (ref "U5") (pin "30") (pinfunction "IO18_30") (pintype "passive"))
    )
    (net (code "30") (name "/SSI_CSN") (class "Default")
      (node (ref "U1") (pin "8") (pinfunction "Z_8") (pintype "passive"))
      (node (ref "U5") (pin "29") (pinfunction "IO5_29") (pintype "passive"))
    )
    (net (code "31") (name "/SSI_DATA") (class "Default")
      (node (ref "U1") (pin "6") (pinfunction "A_6") (pintype "passive"))
      (node (ref "U5") (pin "31") (pinfunction "IO19_31") (pintype "passive"))
    )
    (net (code "32") (name "/TX") (class "Default")
      (node (ref "R12") (pin "1") (pinfunction "1_1") (pintype "passive"))
      (node (ref "U5") (pin "35") (pinfunction "TXD0_35") (pintype "passive"))
      (node (ref "U7") (pin "25") (pinfunction "RXD_25") (pintype "passive"))
    )
    (net (code "33") (name "/UIO0") (class "Default")
      (node (ref "U5") (pin "14") (pinfunction "IO12_14") (pintype "passive"))
      (node (ref "USER1") (pin "1") (pinfunction "1_1") (pintype "passive"))
    )
    (net (code "34") (name "/UIO1") (class "Default")
      (node (ref "U5") (pin "12") (pinfunction "IO27_12") (pintype "passive"))
      (node (ref "USER1") (pin "2") (pinfunction "2_2") (pintype "passive"))
    )
    (net (code "35") (name "/UIO2") (class "Default")
      (node (ref "U5") (pin "11") (pinfunction "IO26_11") (pintype "passive"))
      (node (ref "USER1") (pin "3") (pinfunction "3_3") (pintype "passive"))
    )
    (net (code "36") (name "/UIO3") (class "Default")
      (node (ref "U5") (pin "10") (pinfunction "IO25_10") (pintype "passive"))
      (node (ref "USER2") (pin "1") (pinfunction "1_1") (pintype "passive"))
    )
    (net (code "37") (name "/UIO4") (class "Default")
      (node (ref "U5") (pin "9") (pinfunction "IO33_9") (pintype "passive"))
      (node (ref "USER2") (pin "2") (pinfunction "2_2") (pintype "passive"))
    )
    (net (code "38") (name "/UIO5") (class "Default")
      (node (ref "U5") (pin "16") (pinfunction "IO13_16") (pintype "passive"))
      (node (ref "USER2") (pin "3") (pinfunction "3_3") (pintype "passive"))
    )
    (net (code "39") (name "/VFAN") (class "Default")
      (node (ref "JP1") (pin "2") (pinfunction "C_2") (pintype "passive"))
      (node (ref "SYSFAN1") (pin "2") (pinfunction "2_2") (pintype "passive"))
    )
    (net (code "40") (name "/VPD") (class "Default")
      (node (ref "20V") (pin "2") (pinfunction "2_2") (pintype "passive"))
      (node (ref "C17") (pin "2") (pinfunction "2_2") (pintype "passive"))
      (node (ref "C2") (pin "1") (pinfunction "1_1") (pintype "passive"))
      (node (ref "C22") (pin "1") (pinfunction "1_1") (pintype "passive"))
      (node (ref "C4") (pin "1") (pinfunction "1_1") (pintype "passive"))
      (node (ref "C6") (pin "1") (pinfunction "1_1") (pintype "passive"))
      (node (ref "C8") (pin "1") (pinfunction "1_1") (pintype "passive"))
      (node (ref "PD") (pin "11") (pinfunction "VBUS_11") (pintype "passive"))
      (node (ref "PD") (pin "2") (pinfunction "VBUS_2") (pintype "passive"))
      (node (ref "R11") (pin "2") (pinfunction "2_2") (pintype "passive"))
      (node (ref "R17") (pin "2") (pinfunction "2_2") (pintype "passive"))
      (node (ref "U2") (pin "11") (pinfunction "VM_11") (pintype "passive"))
      (node (ref "U2") (pin "4") (pinfunction "VM_4") (pintype "passive"))
      (node (ref "U3") (pin "7") (pinfunction "VIN_7") (pintype "passive"))
      (node (ref "U6") (pin "7") (pinfunction "VIN_7") (pintype "passive"))
    )
    (net (code "41") (name "/VUSB") (class "Default")
      (node (ref "D1") (pin "1") (pinfunction "A_1") (pintype "passive"))
      (node (ref "DATA") (pin "11") (pinfunction "VBUS_11") (pintype "passive"))
      (node (ref "DATA") (pin "2") (pinfunction "VBUS_2") (pintype "passive"))
      (node (ref "U7") (pin "7") (pinfunction "REGIN_7") (pintype "passive"))
      (node (ref "U7") (pin "8") (pinfunction "VBUS_8") (pintype "passive"))
    )
    (net (code "42") (name "Net-(D2-K)") (class "Default")
      (node (ref "C15") (pin "1") (pinfunction "1_1") (pintype "passive"))
      (node (ref "D2") (pin "1") (pinfunction "K_1") (pintype "passive"))
      (node (ref "L1") (pin "2") (pinfunction "2_2") (pintype "passive"))
      (node (ref "U6") (pin "8") (pinfunction "PH_8") (pintype "passive"))
    )
    (net (code "43") (name "Net-(D3-A)") (class "Default")
      (node (ref "C18") (pin "2") (pinfunction "2_2") (pintype "passive"))
      (node (ref "D3") (pin "1") (pinfunction "A_1") (pintype "passive"))
      (node (ref "L1") (pin "1") (pinfunction "1_1") (pintype "passive"))
      (node (ref "R14") (pin "1") (pinfunction "1_1") (pintype "passive"))
    )
    (net (code "44") (name "Net-(D6-A)") (class "Default")
      (node (ref "C7") (pin "2") (pinfunction "2_2") (pintype "passive"))
      (node (ref "D6") (pin "1") (pinfunction "A_1") (pintype "passive"))
      (node (ref "L3") (pin "1") (pinfunction "1_1") (pintype "passive"))
      (node (ref "R19") (pin "1") (pinfunction "1_1") (pintype "passive"))
    )
    (net (code "45") (name "Net-(D7-K)") (class "Default")
      (node (ref "C12") (pin "1") (pinfunction "1_1") (pintype "passive"))
      (node (ref "D7") (pin "1") (pinfunction "K_1") (pintype "passive"))
      (node (ref "L3") (pin "2") (pinfunction "2_2") (pintype "passive"))
      (node (ref "U3") (pin "8") (pinfunction "PH_8") (pintype "passive"))
    )
    (net (code "46") (name "Net-(DATA-CC1)") (class "Default")
      (node (ref "DATA") (pin "4") (pinfunction "CC1_4") (pintype "passive"))
      (node (ref "R23") (pin "2") (pinfunction "2_2") (pintype "passive"))
    )
    (net (code "47") (name "Net-(DATA-CC2)") (class "Default")
      (node (ref "DATA") (pin "10") (pinfunction "CC2_10") (pintype "passive"))
      (node (ref "R22") (pin "2") (pinfunction "2_2") (pintype "passive"))
    )
    (net (code "48") (name "Net-(PWR-K)") (class "Default")
      (node (ref "PWR") (pin "2") (pinfunction "K_2") (pintype "passive"))
      (node (ref "R9") (pin "2") (pinfunction "2_2") (pintype "passive"))
    )
    (net (code "49") (name "Net-(Q1-B)") (class "Default")
      (node (ref "Q1") (pin "1") (pinfunction "B_1") (pintype "passive"))
      (node (ref "R4") (pin "1") (pinfunction "1_1") (pintype "passive"))
    )
    (net (code "50") (name "Net-(Q2-B)") (class "Default")
      (node (ref "Q2") (pin "1") (pinfunction "B_1") (pintype "passive"))
      (node (ref "R3") (pin "2") (pinfunction "2_2") (pintype "passive"))
    )
    (net (code "51") (name "Net-(R20-Pad1)") (class "Default")
      (node (ref "R20") (pin "1") (pinfunction "1_1") (pintype "passive"))
      (node (ref "R21") (pin "1") (pinfunction "1_1") (pintype "passive"))
    )
    (net (code "52") (name "Net-(R24-Pad2)") (class "Default")
      (node (ref "R24") (pin "2") (pinfunction "2_2") (pintype "passive"))
      (node (ref "R27") (pin "1") (pinfunction "1_1") (pintype "passive"))
    )
    (net (code "53") (name "Net-(U2-CP1)") (class "Default")
      (node (ref "C1") (pin "2") (pinfunction "2_2") (pintype "passive"))
      (node (ref "U2") (pin "1") (pinfunction "CP1_1") (pintype "passive"))
    )
    (net (code "54") (name "Net-(U2-CP2)") (class "Default")
      (node (ref "C1") (pin "1") (pinfunction "1_1") (pintype "passive"))
      (node (ref "U2") (pin "2") (pinfunction "CP2_2") (pintype "passive"))
    )
    (net (code "55") (name "Net-(U2-V3P3OUT)") (class "Default")
      (node (ref "C5") (pin "2") (pinfunction "2_2") (pintype "passive"))
      (node (ref "U2") (pin "15") (pinfunction "V3P3OUT_15") (pintype "passive"))
    )
    (net (code "56") (name "Net-(U2-VCP)") (class "Default")
      (node (ref "C2") (pin "2") (pinfunction "2_2") (pintype "passive"))
      (node (ref "U2") (pin "3") (pinfunction "VCP_3") (pintype "passive"))
    )
    (net (code "57") (name "Net-(U3-BOOT)") (class "Default")
      (node (ref "C12") (pin "2") (pinfunction "2_2") (pintype "passive"))
      (node (ref "U3") (pin "1") (pinfunction "BOOT_1") (pintype "passive"))
    )
    (net (code "58") (name "Net-(U3-VSENSE)") (class "Default")
      (node (ref "R19") (pin "2") (pinfunction "2_2") (pintype "passive"))
      (node (ref "R27") (pin "2") (pinfunction "2_2") (pintype "passive"))
      (node (ref "U3") (pin "4") (pinfunction "VSENSE_4") (pintype "passive"))
    )
    (net (code "59") (name "Net-(U4-VBUS)") (class "Default")
      (node (ref "R17") (pin "1") (pinfunction "1_1") (pintype "passive"))
      (node (ref "U4") (pin "8") (pinfunction "VBUS_8") (pintype "passive"))
    )
    (net (code "60") (name "Net-(U4-VDD)") (class "Default")
      (node (ref "C11") (pin "2") (pinfunction "2_2") (pintype "passive"))
      (node (ref "R11") (pin "1") (pinfunction "1_1") (pintype "passive"))
      (node (ref "U4") (pin "1") (pinfunction "VDD_1") (pintype "passive"))
    )
    (net (code "61") (name "Net-(U6-BOOT)") (class "Default")
      (node (ref "C15") (pin "2") (pinfunction "2_2") (pintype "passive"))
      (node (ref "U6") (pin "1") (pinfunction "BOOT_1") (pintype "passive"))
    )
    (net (code "62") (name "Net-(U6-VSENSE)") (class "Default")
      (node (ref "R14") (pin "2") (pinfunction "2_2") (pintype "passive"))
      (node (ref "R20") (pin "2") (pinfunction "2_2") (pintype "passive"))
      (node (ref "U6") (pin "4") (pinfunction "VSENSE_4") (pintype "passive"))
    )
    (net (code "63") (name "unconnected-(DATA-SBU1-Pad9)") (class "Default")
      (node (ref "DATA") (pin "9") (pinfunction "SBU1_9") (pintype "passive+no_connect"))
    )
    (net (code "64") (name "unconnected-(DATA-SBU2-Pad3)") (class "Default")
      (node (ref "DATA") (pin "3") (pinfunction "SBU2_3") (pintype "passive+no_connect"))
    )
    (net (code "65") (name "unconnected-(PD-DN1-Pad7)") (class "Default")
      (node (ref "PD") (pin "7") (pinfunction "DN1_7") (pintype "passive+no_connect"))
    )
    (net (code "66") (name "unconnected-(PD-DN2-Pad5)") (class "Default")
      (node (ref "PD") (pin "5") (pinfunction "DN2_5") (pintype "passive+no_connect"))
    )
    (net (code "67") (name "unconnected-(PD-DP1-Pad6)") (class "Default")
      (node (ref "PD") (pin "6") (pinfunction "DP1_6") (pintype "passive+no_connect"))
    )
    (net (code "68") (name "unconnected-(PD-DP2-Pad8)") (class "Default")
      (node (ref "PD") (pin "8") (pinfunction "DP2_8") (pintype "passive+no_connect"))
    )
    (net (code "69") (name "unconnected-(PD-SBU1-Pad9)") (class "Default")
      (node (ref "PD") (pin "9") (pinfunction "SBU1_9") (pintype "passive+no_connect"))
    )
    (net (code "70") (name "unconnected-(PD-SBU2-Pad3)") (class "Default")
      (node (ref "PD") (pin "3") (pinfunction "SBU2_3") (pintype "passive+no_connect"))
    )
    (net (code "71") (name "unconnected-(SYSFAN1-Pad3)") (class "Default")
      (node (ref "SYSFAN1") (pin "3") (pinfunction "3_3") (pintype "passive+no_connect"))
    )
    (net (code "72") (name "unconnected-(SYSFAN1-Pad4)") (class "Default")
      (node (ref "SYSFAN1") (pin "4") (pinfunction "4_4") (pintype "passive+no_connect"))
    )
    (net (code "73") (name "unconnected-(U1-EP-Pad17)") (class "Default")
      (node (ref "U1") (pin "17") (pinfunction "EP_17") (pintype "passive+no_connect"))
    )
    (net (code "74") (name "unconnected-(U1-NC-Pad1)") (class "Default")
      (node (ref "U1") (pin "1") (pinfunction "NC_1") (pintype "passive+no_connect"))
    )
    (net (code "75") (name "unconnected-(U1-NC-Pad2)") (class "Default")
      (node (ref "U1") (pin "2") (pinfunction "NC_2") (pintype "passive+no_connect"))
    )
    (net (code "76") (name "unconnected-(U1-NC-Pad3)") (class "Default")
      (node (ref "U1") (pin "3") (pinfunction "NC_3") (pintype "passive+no_connect"))
    )
    (net (code "77") (name "unconnected-(U1-NC-Pad4)") (class "Default")
      (node (ref "U1") (pin "4") (pinfunction "NC_4") (pintype "passive+no_connect"))
    )
    (net (code "78") (name "unconnected-(U1-NC-Pad10)") (class "Default")
      (node (ref "U1") (pin "10") (pinfunction "NC_10") (pintype "passive+no_connect"))
    )
    (net (code "79") (name "unconnected-(U1-OUT-Pad15)") (class "Default")
      (node (ref "U1") (pin "15") (pinfunction "OUT_15") (pintype "passive+no_connect"))
    )
    (net (code "80") (name "unconnected-(U1-PUSH-Pad5)") (class "Default")
      (node (ref "U1") (pin "5") (pinfunction "PUSH_5") (pintype "passive+no_connect"))
    )
    (net (code "81") (name "unconnected-(U1-U-Pad11)") (class "Default")
      (node (ref "U1") (pin "11") (pinfunction "U_11") (pintype "passive+no_connect"))
    )
    (net (code "82") (name "unconnected-(U1-V-Pad12)") (class "Default")
      (node (ref "U1") (pin "12") (pinfunction "V_12") (pintype "passive+no_connect"))
    )
    (net (code "83") (name "unconnected-(U1-W-Pad9)") (class "Default")
      (node (ref "U1") (pin "9") (pinfunction "W_9") (pintype "passive+no_connect"))
    )
    (net (code "84") (name "unconnected-(U2-COMPO#-Pad19)") (class "Default")
      (node (ref "U2") (pin "19") (pinfunction "COMPO#_19") (pintype "passive+no_connect"))
    )
    (net (code "85") (name "unconnected-(U2-NC-Pad21)") (class "Default")
      (node (ref "U2") (pin "21") (pinfunction "NC_21") (pintype "passive+no_connect"))
    )
    (net (code "86") (name "unconnected-(U3-ENA-Pad5)") (class "Default")
      (node (ref "U3") (pin "5") (pinfunction "ENA_5") (pintype "passive+no_connect"))
    )
    (net (code "87") (name "unconnected-(U3-NC-Pad2)") (class "Default")
      (node (ref "U3") (pin "2") (pinfunction "NC_2") (pintype "passive+no_connect"))
    )
    (net (code "88") (name "unconnected-(U3-NC-Pad3)") (class "Default")
      (node (ref "U3") (pin "3") (pinfunction "NC_3") (pintype "passive+no_connect"))
    )
    (net (code "89") (name "unconnected-(U4-CFG1-Pad9)") (class "Default")
      (node (ref "U4") (pin "9") (pinfunction "CFG1_9") (pintype "passive+no_connect"))
    )
    (net (code "90") (name "unconnected-(U4-CFG2-Pad2)") (class "Default")
      (node (ref "U4") (pin "2") (pinfunction "CFG2_2") (pintype "passive+no_connect"))
    )
    (net (code "91") (name "unconnected-(U4-CFG3-Pad3)") (class "Default")
      (node (ref "U4") (pin "3") (pinfunction "CFG3_3") (pintype "passive+no_connect"))
    )
    (net (code "92") (name "unconnected-(U4-DM-Pad5)") (class "Default")
      (node (ref "U4") (pin "5") (pinfunction "DM_5") (pintype "passive+no_connect"))
    )
    (net (code "93") (name "unconnected-(U4-DP-Pad4)") (class "Default")
      (node (ref "U4") (pin "4") (pinfunction "DP_4") (pintype "passive+no_connect"))
    )
    (net (code "94") (name "unconnected-(U4-PG-Pad10)") (class "Default")
      (node (ref "U4") (pin "10") (pinfunction "PG_10") (pintype "passive+no_connect"))
    )
    (net (code "95") (name "unconnected-(U5-IO23-Pad37)") (class "Default")
      (node (ref "U5") (pin "37") (pinfunction "IO23_37") (pintype "passive+no_connect"))
    )
    (net (code "96") (name "unconnected-(U5-IO32-Pad8)") (class "Default")
      (node (ref "U5") (pin "8") (pinfunction "IO32_8") (pintype "passive+no_connect"))
    )
    (net (code "97") (name "unconnected-(U5-IO34-Pad6)") (class "Default")
      (node (ref "U5") (pin "6") (pinfunction "IO34_6") (pintype "passive+no_connect"))
    )
    (net (code "98") (name "unconnected-(U5-IO35-Pad7)") (class "Default")
      (node (ref "U5") (pin "7") (pinfunction "IO35_7") (pintype "passive+no_connect"))
    )
    (net (code "99") (name "unconnected-(U5-NC-Pad17)") (class "Default")
      (node (ref "U5") (pin "17") (pinfunction "NC_17") (pintype "passive+no_connect"))
    )
    (net (code "100") (name "unconnected-(U5-NC-Pad18)") (class "Default")
      (node (ref "U5") (pin "18") (pinfunction "NC_18") (pintype "passive+no_connect"))
    )
    (net (code "101") (name "unconnected-(U5-NC-Pad19)") (class "Default")
      (node (ref "U5") (pin "19") (pinfunction "NC_19") (pintype "passive+no_connect"))
    )
    (net (code "102") (name "unconnected-(U5-NC-Pad20)") (class "Default")
      (node (ref "U5") (pin "20") (pinfunction "NC_20") (pintype "passive+no_connect"))
    )
    (net (code "103") (name "unconnected-(U5-NC-Pad21)") (class "Default")
      (node (ref "U5") (pin "21") (pinfunction "NC_21") (pintype "passive+no_connect"))
    )
    (net (code "104") (name "unconnected-(U5-NC-Pad22)") (class "Default")
      (node (ref "U5") (pin "22") (pinfunction "NC_22") (pintype "passive+no_connect"))
    )
    (net (code "105") (name "unconnected-(U5-NC-Pad32)") (class "Default")
      (node (ref "U5") (pin "32") (pinfunction "NC_32") (pintype "passive+no_connect"))
    )
    (net (code "106") (name "unconnected-(U5-SENSOR_VN-Pad5)") (class "Default")
      (node (ref "U5") (pin "5") (pinfunction "SENSOR_VN_5") (pintype "passive+no_connect"))
    )
    (net (code "107") (name "unconnected-(U5-SENSOR_VP-Pad4)") (class "Default")
      (node (ref "U5") (pin "4") (pinfunction "SENSOR_VP_4") (pintype "passive+no_connect"))
    )
    (net (code "108") (name "unconnected-(U6-ENA-Pad5)") (class "Default")
      (node (ref "U6") (pin "5") (pinfunction "ENA_5") (pintype "passive+no_connect"))
    )
    (net (code "109") (name "unconnected-(U6-NC-Pad2)") (class "Default")
      (node (ref "U6") (pin "2") (pinfunction "NC_2") (pintype "passive+no_connect"))
    )
    (net (code "110") (name "unconnected-(U6-NC-Pad3)") (class "Default")
      (node (ref "U6") (pin "3") (pinfunction "NC_3") (pintype "passive+no_connect"))
    )
    (net (code "111") (name "unconnected-(U7-CTS-Pad23)") (class "Default")
      (node (ref "U7") (pin "23") (pinfunction "CTS_23") (pintype "passive+no_connect"))
    )
    (net (code "112") (name "unconnected-(U7-DCD-Pad1)") (class "Default")
      (node (ref "U7") (pin "1") (pinfunction "DCD_1") (pintype "passive+no_connect"))
    )
    (net (code "113") (name "unconnected-(U7-DSR-Pad27)") (class "Default")
      (node (ref "U7") (pin "27") (pinfunction "DSR_27") (pintype "passive+no_connect"))
    )
    (net (code "114") (name "unconnected-(U7-NC-Pad10)") (class "Default")
      (node (ref "U7") (pin "10") (pinfunction "NC_10") (pintype "passive+no_connect"))
    )
    (net (code "115") (name "unconnected-(U7-NC-Pad13)") (class "Default")
      (node (ref "U7") (pin "13") (pinfunction "NC_13") (pintype "passive+no_connect"))
    )
    (net (code "116") (name "unconnected-(U7-NC-Pad14)") (class "Default")
      (node (ref "U7") (pin "14") (pinfunction "NC_14") (pintype "passive+no_connect"))
    )
    (net (code "117") (name "unconnected-(U7-NC-Pad15)") (class "Default")
      (node (ref "U7") (pin "15") (pinfunction "NC_15") (pintype "passive+no_connect"))
    )
    (net (code "118") (name "unconnected-(U7-NC-Pad16)") (class "Default")
      (node (ref "U7") (pin "16") (pinfunction "NC_16") (pintype "passive+no_connect"))
    )
    (net (code "119") (name "unconnected-(U7-NC-Pad17)") (class "Default")
      (node (ref "U7") (pin "17") (pinfunction "NC_17") (pintype "passive+no_connect"))
    )
    (net (code "120") (name "unconnected-(U7-NC-Pad18)") (class "Default")
      (node (ref "U7") (pin "18") (pinfunction "NC_18") (pintype "passive+no_connect"))
    )
    (net (code "121") (name "unconnected-(U7-NC-Pad19)") (class "Default")
      (node (ref "U7") (pin "19") (pinfunction "NC_19") (pintype "passive+no_connect"))
    )
    (net (code "122") (name "unconnected-(U7-NC-Pad20)") (class "Default")
      (node (ref "U7") (pin "20") (pinfunction "NC_20") (pintype "passive+no_connect"))
    )
    (net (code "123") (name "unconnected-(U7-NC-Pad21)") (class "Default")
      (node (ref "U7") (pin "21") (pinfunction "NC_21") (pintype "passive+no_connect"))
    )
    (net (code "124") (name "unconnected-(U7-NC-Pad22)") (class "Default")
      (node (ref "U7") (pin "22") (pinfunction "NC_22") (pintype "passive+no_connect"))
    )
    (net (code "125") (name "unconnected-(U7-RI-Pad2)") (class "Default")
      (node (ref "U7") (pin "2") (pinfunction "RI_2") (pintype "passive+no_connect"))
    )
    (net (code "126") (name "unconnected-(U7-SUSPEND#-Pad11)") (class "Default")
      (node (ref "U7") (pin "11") (pinfunction "SUSPEND#_11") (pintype "passive+no_connect"))
    )
    (net (code "127") (name "unconnected-(U7-SUSPEND-Pad12)") (class "Default")
      (node (ref "U7") (pin "12") (pinfunction "SUSPEND_12") (pintype "passive+no_connect"))
    )
  )
)
